# AGC-Amplifier-LM13600-Monosch.net
KiCad netlist of a schematic drawn in EAGLE
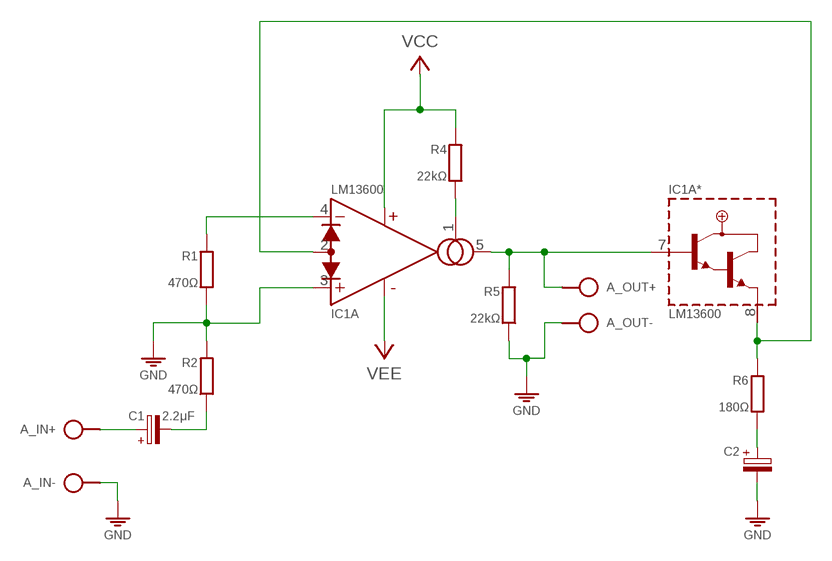
[diagram p0: schematic, sheet 1]

(export (version "E")
  (design (tool "Eeschema 10.0.6"))
  (components
    (comp (ref "A_IN")
      (value "SPAD+--+")
      (footprint "eagle-import:SPAD-+")
      (libsource (lib "eagle-import") (part "SPAD+--+"))
    )
    (comp (ref "A_OUT")
      (value "SPAD+-+-")
      (footprint "eagle-import:SPAD+-")
      (libsource (lib "eagle-import") (part "SPAD+-+-"))
    )
    (comp (ref "C1")
      (value "2.2μF")
      (footprint "eagle-import:E2,5-4")
      (libsource (lib "eagle-import") (part "CPOL-HE2,5-4"))
    )
    (comp (ref "C2")
      (value "CPOLE2,5-4/V")
      (footprint "eagle-import:E2.5-4_V")
      (libsource (lib "eagle-import") (part "CPOLE2,5-4/V"))
    )
    (comp (ref "IC1")
      (value "LM13600")
      (footprint "eagle-import:DIL16")
      (libsource (lib "eagle-import") (part "LM13600"))
    )
    (comp (ref "R1")
      (value "470Ω")
      (footprint "eagle-import:0204_10-V")
      (libsource (lib "eagle-import") (part "R0204/10-V"))
    )
    (comp (ref "R2")
      (value "470Ω")
      (footprint "eagle-import:0204_10-V")
      (libsource (lib "eagle-import") (part "R0204/10-V"))
    )
    (comp (ref "R4")
      (value "22kΩ")
      (footprint "eagle-import:0204_10-V")
      (libsource (lib "eagle-import") (part "R0204/10-V"))
    )
    (comp (ref "R5")
      (value "22kΩ")
      (footprint "eagle-import:0204_10-V")
      (libsource (lib "eagle-import") (part "R0204/10-V"))
    )
    (comp (ref "R6")
      (value "180Ω")
      (footprint "eagle-import:0204_10-V")
      (libsource (lib "eagle-import") (part "R0204/10-V"))
    )
    (comp (ref "U$3")
      (value "VCC_GND_VEE")
      (footprint "eagle-import:SPAD-3")
      (libsource (lib "eagle-import") (part "VCC_GND_VEE"))
    )
  )
  (nets
    (net (code "1") (name "GND") (class "Default")
      (node (ref "A_IN") (pin "1") (pinfunction "P$1_1") (pintype "passive"))
      (node (ref "A_OUT") (pin "1") (pinfunction "P$1_1") (pintype "passive"))
      (node (ref "C2") (pin "-") (pinfunction "-_-") (pintype "passive"))
      (node (ref "IC1") (pin "3") (pinfunction "+IN_3") (pintype "input"))
      (node (ref "R1") (pin "2") (pinfunction "2_2") (pintype "passive"))
      (node (ref "R2") (pin "1") (pinfunction "1_1") (pintype "passive"))
      (node (ref "R5") (pin "2") (pinfunction "2_2") (pintype "passive"))
      (node (ref "U$3") (pin "2") (pinfunction "GND_2") (pintype "power_in"))
    )
    (net (code "2") (name "Net-(A_INA-P$1)") (class "Default")
      (node (ref "A_IN") (pin "2") (pinfunction "P$1_2") (pintype "passive"))
      (node (ref "C1") (pin "+") (pinfunction "+_+") (pintype "passive"))
    )
    (net (code "3") (name "Net-(A_OUTA-P$1)") (class "Default")
      (node (ref "A_OUT") (pin "2") (pinfunction "P$1_2") (pintype "passive"))
      (node (ref "IC1") (pin "5") (pinfunction "OUT_5") (pintype "output"))
      (node (ref "IC1") (pin "7") (pinfunction "BUFF/IN_7") (pintype "input"))
      (node (ref "R5") (pin "1") (pinfunction "1_1") (pintype "passive"))
    )
    (net (code "4") (name "Net-(C1-Pad-)") (class "Default")
      (node (ref "C1") (pin "-") (pinfunction "-_-") (pintype "passive"))
      (node (ref "R2") (pin "2") (pinfunction "2_2") (pintype "passive"))
    )
    (net (code "5") (name "Net-(C2-Pad+)") (class "Default")
      (node (ref "C2") (pin "+") (pinfunction "+_+") (pintype "passive"))
      (node (ref "R6") (pin "2") (pinfunction "2_2") (pintype "passive"))
    )
    (net (code "6") (name "Net-(IC1A-V+)") (class "Default")
      (node (ref "IC1") (pin "11") (pinfunction "V+_11") (pintype "power_in"))
      (node (ref "R4") (pin "1") (pinfunction "1_1") (pintype "passive"))
      (node (ref "U$3") (pin "1") (pinfunction "VCC_1") (pintype "power_in"))
    )
    (net (code "7") (name "Net-(IC1A-V-)") (class "Default")
      (node (ref "IC1") (pin "6") (pinfunction "V-_6") (pintype "power_in"))
      (node (ref "U$3") (pin "3") (pinfunction "VEE_3") (pintype "power_in"))
    )
    (net (code "8") (name "Net-(IC1B--IN)") (class "Default")
      (node (ref "IC1") (pin "4") (pinfunction "-IN_4") (pintype "input"))
      (node (ref "R1") (pin "1") (pinfunction "1_1") (pintype "passive"))
    )
    (net (code "9") (name "Net-(IC1B-AMP{slash}BIAS)") (class "Default")
      (node (ref "IC1") (pin "1") (pinfunction "AMP/BIAS_1") (pintype "input"))
      (node (ref "R4") (pin "2") (pinfunction "2_2") (pintype "passive"))
    )
    (net (code "10") (name "Net-(IC1B-DIODE{slash}BIAS)") (class "Default")
      (node (ref "IC1") (pin "2") (pinfunction "DIODE/BIAS_2") (pintype "input"))
      (node (ref "IC1") (pin "8") (pinfunction "BUFF/OUT_8") (pintype "output"))
      (node (ref "R6") (pin "1") (pinfunction "1_1") (pintype "passive"))
    )
  )
)
